# Power_Outputs.net
KiCad netlist of a schematic drawn in Altium Designer
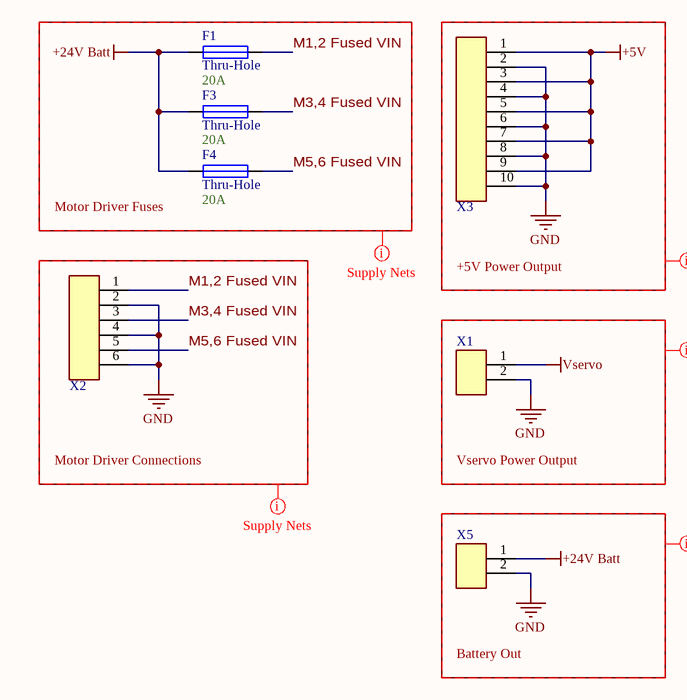
[diagram p0: Power Outputs.SchDoc]

(export (version "E")
  (design (tool "Eeschema 10.0.6"))
  (components
    (comp (ref "F1")
      (value "Thru-Hole")
      (footprint "[Fuse] Thru-Hole Blade")
      (fields (field (name "CAPACITY") "20A"))
      (libsource (lib "RADM Components") (part "[Fuse] Thru-Hole Blade"))
    )
    (comp (ref "F3")
      (value "Thru-Hole")
      (footprint "[Fuse] Thru-Hole Blade")
      (fields (field (name "CAPACITY") "20A"))
      (libsource (lib "RADM Components") (part "[Fuse] Thru-Hole Blade"))
    )
    (comp (ref "F4")
      (value "Thru-Hole")
      (footprint "[Fuse] Thru-Hole Blade")
      (fields (field (name "CAPACITY") "20A"))
      (libsource (lib "RADM Components") (part "[Fuse] Thru-Hole Blade"))
    )
    (comp (ref "X1")
      (value "2pin Screw Terminal")
      (footprint "[Screw Terminal] 2pin 5mm")
      (libsource (lib "RADM Connectors") (part "[Screw Terminal] 2pin"))
    )
    (comp (ref "X2")
      (value "[Screw Terminal] 6pin")
      (footprint "[Screw Terminal] 6pin")
      (description "x3")
      (libsource (lib "RADM Connectors") (part "[Screw Terminal] 6pin"))
    )
    (comp (ref "X3")
      (value "[Screw Terminal] 10pin")
      (footprint "[Screw Terminal] 10pin")
      (description "x5")
      (libsource (lib "RADM Connectors") (part "[Screw Terminal] 10pin"))
    )
    (comp (ref "X5")
      (value "2pin Screw Terminal")
      (footprint "[Screw Terminal] 2pin 5mm")
      (libsource (lib "RADM Connectors") (part "[Screw Terminal] 2pin"))
    )
  )
  (nets
    (net (code "1") (name "+5V") (class "Default")
      (node (ref "X3") (pin "1") (pintype "power_in"))
      (node (ref "X3") (pin "3") (pintype "power_in"))
      (node (ref "X3") (pin "5") (pintype "power_in"))
      (node (ref "X3") (pin "7") (pintype "power_in"))
      (node (ref "X3") (pin "9") (pintype "power_in"))
    )
    (net (code "2") (name "+24V Batt") (class "Default")
      (node (ref "F1") (pin "1") (pinfunction "1_1") (pintype "passive"))
      (node (ref "F3") (pin "1") (pinfunction "1_1") (pintype "passive"))
      (node (ref "F4") (pin "1") (pinfunction "1_1") (pintype "passive"))
      (node (ref "X5") (pin "1") (pintype "power_in"))
    )
    (net (code "3") (name "/M1,2 Fused VIN") (class "Default")
      (node (ref "F1") (pin "2") (pinfunction "2_2") (pintype "passive"))
      (node (ref "X2") (pin "1") (pintype "power_in"))
    )
    (net (code "4") (name "/M3,4 Fused VIN") (class "Default")
      (node (ref "F3") (pin "2") (pinfunction "2_2") (pintype "passive"))
      (node (ref "X2") (pin "3") (pintype "power_in"))
    )
    (net (code "5") (name "/M5,6 Fused VIN") (class "Default")
      (node (ref "F4") (pin "2") (pinfunction "2_2") (pintype "passive"))
      (node (ref "X2") (pin "5") (pintype "power_in"))
    )
    (net (code "6") (name "GND") (class "Default")
      (node (ref "X1") (pin "2") (pintype "power_in"))
      (node (ref "X2") (pin "2") (pintype "power_in"))
      (node (ref "X2") (pin "4") (pintype "power_in"))
      (node (ref "X2") (pin "6") (pintype "power_in"))
      (node (ref "X3") (pin "10") (pintype "power_in"))
      (node (ref "X3") (pin "2") (pintype "power_in"))
      (node (ref "X3") (pin "4") (pintype "power_in"))
      (node (ref "X3") (pin "6") (pintype "power_in"))
      (node (ref "X3") (pin "8") (pintype "power_in"))
      (node (ref "X5") (pin "2") (pintype "power_in"))
    )
    (net (code "7") (name "Vservo") (class "Default") (node (ref "X1") (pin "1") (pintype "power_in")))
  )
)
